# CH32F203VCT6-R1.net
KiCad netlist of a schematic drawn in Altium Designer
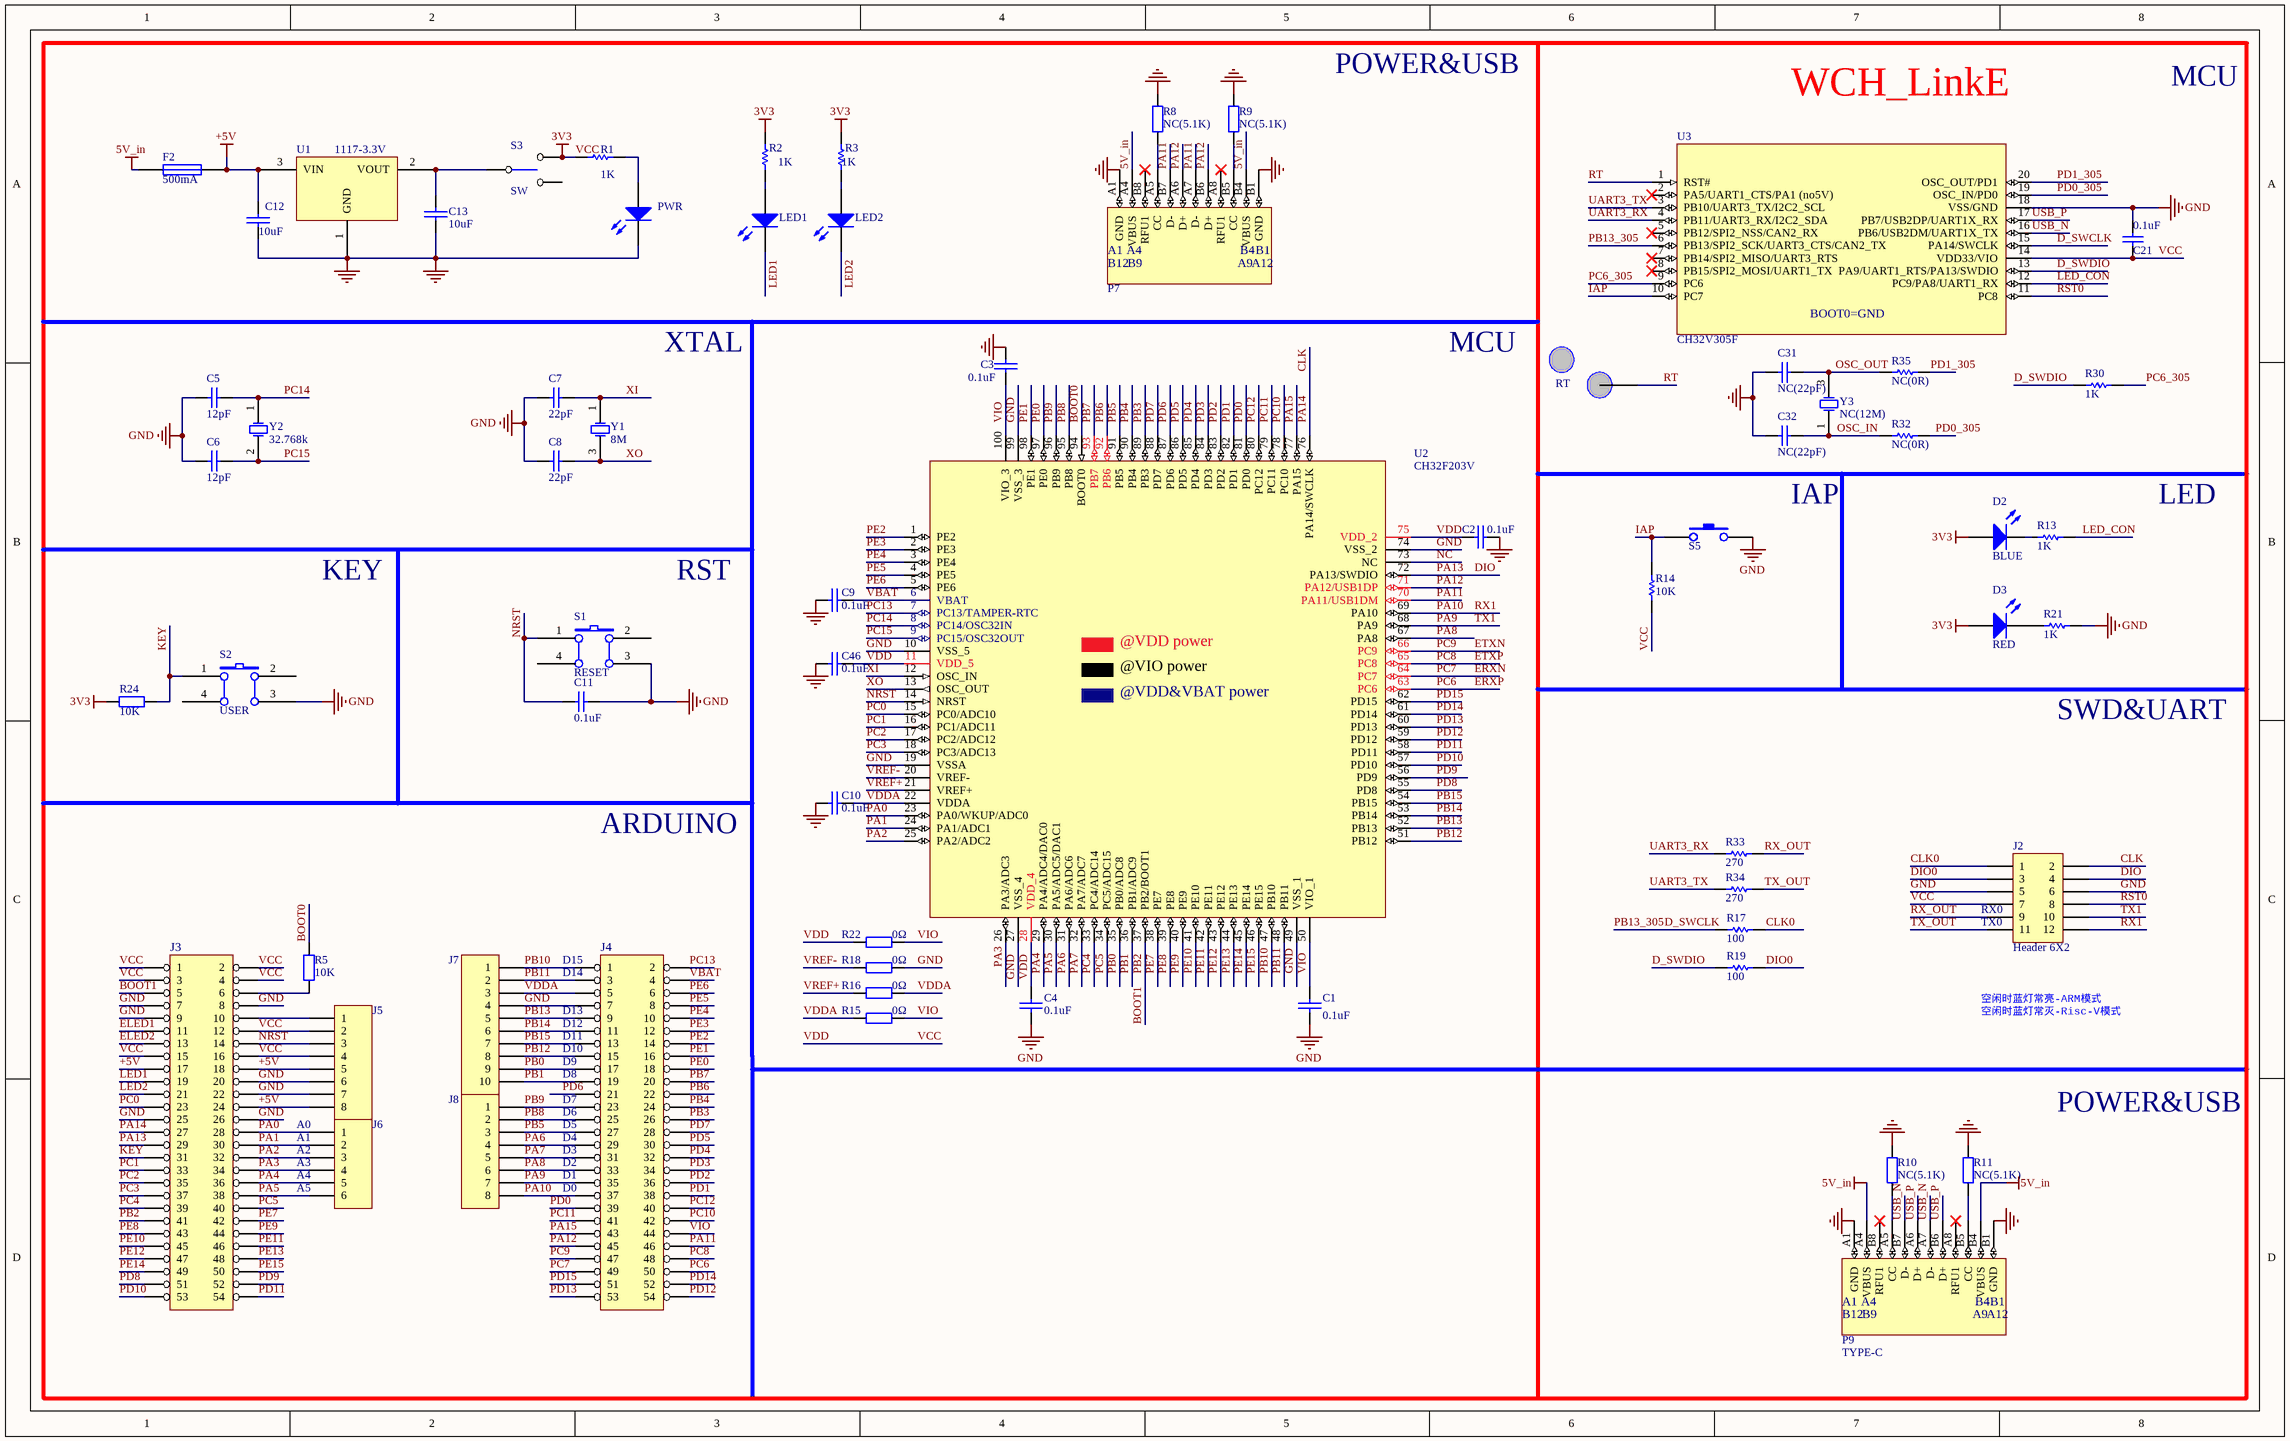
[diagram p0: CH32F203VCT6-R1.SchDoc]

(export (version "E")
  (design (tool "Eeschema 10.0.6"))
  (components
    (comp (ref "C1")
      (value "0.1uF")
      (footprint "0603_C")
      (description "Capacitor")
      (libsource (lib "*") (part "CAP"))
    )
    (comp (ref "C2")
      (value "0.1uF")
      (footprint "0603_C")
      (description "Capacitor")
      (libsource (lib "*") (part "CAP"))
    )
    (comp (ref "C3")
      (value "0.1uF")
      (footprint "0603_C")
      (description "Capacitor")
      (libsource (lib "*") (part "CAP"))
    )
    (comp (ref "C4")
      (value "0.1uF")
      (footprint "0603_C")
      (description "Capacitor")
      (libsource (lib "*") (part "CAP"))
    )
    (comp (ref "C5")
      (value "12pF")
      (footprint "0603_C")
      (description "Capacitor")
      (libsource (lib "Miscellaneous Devices") (part "Cap"))
    )
    (comp (ref "C6")
      (value "12pF")
      (footprint "0603_C")
      (description "Capacitor")
      (libsource (lib "Miscellaneous Devices") (part "Cap"))
    )
    (comp (ref "C7")
      (value "22pF")
      (footprint "0603_C")
      (description "Capacitor")
      (libsource (lib "Miscellaneous Devices") (part "Cap"))
    )
    (comp (ref "C8")
      (value "22pF")
      (footprint "0603_C")
      (description "Capacitor")
      (libsource (lib "Miscellaneous Devices") (part "Cap"))
    )
    (comp (ref "C9")
      (value "0.1uF")
      (footprint "0603_C")
      (description "Capacitor")
      (libsource (lib "*") (part "CAP"))
    )
    (comp (ref "C10")
      (value "0.1uF")
      (footprint "0603_C")
      (description "Capacitor")
      (libsource (lib "*") (part "CAP"))
    )
    (comp (ref "C11")
      (value "0.1uF")
      (footprint "0603_C")
      (description "Capacitor")
      (libsource (lib "Miscellaneous Devices") (part "Cap"))
    )
    (comp (ref "C12")
      (value "10uF")
      (footprint "3216_C")
      (description "Capacitor")
      (libsource (lib "*") (part "CAP"))
    )
    (comp (ref "C13")
      (value "10uF")
      (footprint "3216_C")
      (description "Capacitor")
      (libsource (lib "*") (part "CAP"))
    )
    (comp (ref "C21")
      (value "0.1uF")
      (footprint "0603_C")
      (description "Capacitor")
      (libsource (lib "Miscellaneous Devices") (part "Cap"))
    )
    (comp (ref "C31")
      (value "NC(22pF)")
      (footprint "0603_C")
      (description "Capacitor")
      (fields (field (name "PUBLISHER") "Altium Limited"))
      (libsource (lib "*") (part "Cap"))
    )
    (comp (ref "C32")
      (value "NC(22pF)")
      (footprint "0603_C")
      (description "Capacitor")
      (fields (field (name "PUBLISHER") "Altium Limited"))
      (libsource (lib "*") (part "Cap"))
    )
    (comp (ref "C46")
      (value "0.1uF")
      (footprint "0603_C")
      (description "Capacitor")
      (libsource (lib "*") (part "CAP"))
    )
    (comp (ref "D2")
      (value "BLUE")
      (footprint "0603+")
      (description "Typical RED, GREEN, YELLOW, AMBER GaAs LED")
      (fields (field (name "PUBLISHER") "Altium Limited"))
      (libsource (lib "MYLIB") (part "D0603"))
    )
    (comp (ref "D3")
      (value "RED")
      (footprint "0603+")
      (description "Typical RED, GREEN, YELLOW, AMBER GaAs LED")
      (fields (field (name "PUBLISHER") "Altium Limited"))
      (libsource (lib "MYLIB") (part "D0603"))
    )
    (comp (ref "F2")
      (value "500mA")
      (footprint "0805")
      (description "Fuse")
      (libsource (lib "*") (part "FUSE1"))
    )
    (comp (ref "J2")
      (value "Header 6X2")
      (footprint "IDC12-2.54mm")
      (description "Header, 6-Pin, Dual row")
      (fields (field (name "PUBLISHER") "Altium Limited"))
      (libsource (lib "Miscellaneous Connectors") (part "Header 6X2"))
    )
    (comp (ref "J3")
      (value "HEADER 27x2")
      (footprint "MYPCB:IDC54-2.54MM")
      (description "Header, 27-Pin, Dual row")
      (libsource (lib "wch_sch_others") (part "HEADER 27x2"))
    )
    (comp (ref "J4")
      (value "HEADER 27x2")
      (footprint "MYPCB:IDC54-2.54MM")
      (description "Header, 27-Pin, Dual row")
      (libsource (lib "wch_sch_others") (part "HEADER 27x2"))
    )
    (comp (ref "J5")
      (value "Header 8")
      (footprint "SIP8-2.54mm")
      (description "Header, 8-Pin")
      (fields (field (name "PUBLISHER") "Altium Limited"))
      (libsource (lib "") (part "Header 8_1"))
    )
    (comp (ref "J6")
      (value "Header 6")
      (footprint "SIP6-2.54MM")
      (description "Header, 6-Pin")
      (fields (field (name "PUBLISHER") "Altium Limited"))
      (libsource (lib "Miscellaneous Connectors") (part "Header 6"))
    )
    (comp (ref "J7")
      (value "Header 10")
      (footprint "SIP10-2.54mm")
      (description "Header, 10-Pin")
      (fields (field (name "PUBLISHER") "Altium Limited"))
      (libsource (lib "Miscellaneous Connectors") (part "Header 10"))
    )
    (comp (ref "J8")
      (value "Header 8")
      (footprint "SIP8-2.54mm")
      (description "Header, 8-Pin")
      (fields (field (name "PUBLISHER") "Altium Limited"))
      (libsource (lib "Miscellaneous Connectors") (part "Header 8"))
    )
    (comp (ref "LED1")
      (value "LED1   blue")
      (footprint "0603+")
      (description "Typical INFRARED GaAs LED")
      (fields (field (name "PUBLISHER") "Altium Limited"))
      (libsource (lib "Miscellaneous Devices") (part "LED0"))
    )
    (comp (ref "LED2")
      (value "LED2  blue")
      (footprint "0603+")
      (description "Typical INFRARED GaAs LED")
      (fields (field (name "PUBLISHER") "Altium Limited"))
      (libsource (lib "Miscellaneous Devices") (part "LED0"))
    )
    (comp (ref "P7")
      (value "USBFS")
      (footprint "TYPE-C-Receptacle-2.0")
      (libsource (lib "*") (part "TYPE-C1"))
    )
    (comp (ref "P9")
      (value "TYPE-C")
      (footprint "TYPE-C-Receptacle-2.0")
      (libsource (lib "*") (part "TYPE-C1"))
    )
    (comp (ref "PWR")
      (value "POWER  red")
      (footprint "0603+")
      (description "Typical INFRARED GaAs LED")
      (fields (field (name "PUBLISHER") "Altium Limited"))
      (libsource (lib "Miscellaneous Devices") (part "LED0"))
    )
    (comp (ref "R1")
      (value "1K")
      (footprint "0603")
      (description "Semiconductor Resistor")
      (libsource (lib "Miscellaneous Devices") (part "Res Semi"))
    )
    (comp (ref "R2")
      (value "1K")
      (footprint "0603")
      (description "Semiconductor Resistor")
      (libsource (lib "Miscellaneous Devices") (part "Res Semi"))
    )
    (comp (ref "R3")
      (value "1K")
      (footprint "0603")
      (description "Semiconductor Resistor")
      (libsource (lib "Miscellaneous Devices") (part "Res Semi"))
    )
    (comp (ref "R5")
      (value "10K")
      (footprint "0603")
      (description "Resistor")
      (libsource (lib "Miscellaneous Devices") (part "Res2"))
    )
    (comp (ref "R8")
      (value "NC(5.1K)")
      (footprint "0603")
      (description "Resistor")
      (libsource (lib "") (part "Res2_2"))
    )
    (comp (ref "R9")
      (value "NC(5.1K)")
      (footprint "0603")
      (description "Resistor")
      (libsource (lib "") (part "Res2_2"))
    )
    (comp (ref "R10")
      (value "NC(5.1K)")
      (footprint "0603")
      (description "Resistor")
      (libsource (lib "Miscellaneous Devices") (part "Res2"))
    )
    (comp (ref "R11")
      (value "NC(5.1K)")
      (footprint "0603")
      (description "Resistor")
      (libsource (lib "Miscellaneous Devices") (part "Res2"))
    )
    (comp (ref "R13")
      (value "1K")
      (footprint "0603")
      (description "Resistor")
      (fields (field (name "PUBLISHER") "Altium Limited"))
      (libsource (lib "MYLIB") (part "0603-1"))
    )
    (comp (ref "R14")
      (value "10K")
      (footprint "0603")
      (description "Resistor")
      (fields (field (name "PUBLISHER") "Altium Limited"))
      (libsource (lib "MYLIB") (part "0603-1"))
    )
    (comp (ref "R15")
      (value "0Ω")
      (footprint "0603")
      (description "Resistor")
      (libsource (lib "") (part "Res2_1"))
    )
    (comp (ref "R16")
      (value "0Ω")
      (footprint "0603")
      (description "Resistor")
      (libsource (lib "") (part "Res2_1"))
    )
    (comp (ref "R17")
      (value "100")
      (footprint "0603")
      (description "Resistor")
      (fields (field (name "PUBLISHER") "Altium Limited"))
      (libsource (lib "MYLIB") (part "0603-1"))
    )
    (comp (ref "R18")
      (value "0Ω")
      (footprint "0603")
      (description "Resistor")
      (libsource (lib "") (part "Res2_1"))
    )
    (comp (ref "R19")
      (value "100")
      (footprint "0603")
      (description "Resistor")
      (fields (field (name "PUBLISHER") "Altium Limited"))
      (libsource (lib "MYLIB") (part "0603-1"))
    )
    (comp (ref "R21")
      (value "1K")
      (footprint "0603")
      (description "Resistor")
      (fields (field (name "PUBLISHER") "Altium Limited"))
      (libsource (lib "MYLIB") (part "0603-1"))
    )
    (comp (ref "R22")
      (value "0Ω")
      (footprint "0603")
      (description "Resistor")
      (libsource (lib "") (part "Res2_1"))
    )
    (comp (ref "R24")
      (value "10K")
      (footprint "0603")
      (description "Resistor")
      (libsource (lib "") (part "Res2_1"))
    )
    (comp (ref "R30")
      (value "1K")
      (footprint "0603")
      (description "Resistor")
      (fields (field (name "PUBLISHER") "Altium Limited"))
      (libsource (lib "MYLIB") (part "0603-1"))
    )
    (comp (ref "R32")
      (value "NC(0R)")
      (footprint "0603")
      (description "Resistor")
      (fields (field (name "PUBLISHER") "Altium Limited"))
      (libsource (lib "MYLIB") (part "0603-1"))
    )
    (comp (ref "R33")
      (value "270")
      (footprint "0603")
      (description "Resistor")
      (fields (field (name "PUBLISHER") "Altium Limited"))
      (libsource (lib "MYLIB") (part "0603-1"))
    )
    (comp (ref "R34")
      (value "270")
      (footprint "0603")
      (description "Resistor")
      (fields (field (name "PUBLISHER") "Altium Limited"))
      (libsource (lib "MYLIB") (part "0603-1"))
    )
    (comp (ref "R35")
      (value "NC(0R)")
      (footprint "0603")
      (description "Resistor")
      (fields (field (name "PUBLISHER") "Altium Limited"))
      (libsource (lib "MYLIB") (part "0603-1"))
    )
    (comp (ref "RT")
      (value "Testpoint")
      (footprint "TESTPOINT1")
      (description "测试点")
      (libsource (lib "wch_sch_others") (part "Testpoint"))
    )
    (comp (ref "S1")
      (value "RESET")
      (footprint "KEYX")
      (description "SE PUSHBUTTON")
      (libsource (lib "Documents") (part "SW PUSHBUTTON"))
    )
    (comp (ref "S2")
      (value "USER")
      (footprint "KEYX")
      (description "SE PUSHBUTTON")
      (libsource (lib "Documents") (part "SW PUSHBUTTON"))
    )
    (comp (ref "S3") (value "SW") (footprint "SW1") (libsource (lib "MYSCH") (part "SW")))
    (comp (ref "S5") (value "KEY") (footprint "贴片按键") (libsource (lib "*") (part "KEY")))
    (comp (ref "U1")
      (value "1117-3.3V")
      (footprint "SOT-223")
      (libsource (lib "wch_sch_others") (part "1117-3.3V"))
    )
    (comp (ref "U2")
      (value "CH32F203V")
      (footprint "LQFP100")
      (description "ARM M3 HD-MCU, 144MHz, 8*UART, 10*Timer, 4*OPA")
      (libsource (lib "CHXXX") (part "CH32F203V"))
    )
    (comp (ref "U3")
      (value "CH32V305F")
      (footprint "TSSOP20")
      (description "RISC-V FPU HD-MCU, 144MHz, USB_480M, CAN, UART*2, SPI")
      (libsource (lib "CHXXX") (part "CH32V305F"))
    )
    (comp (ref "Y1")
      (value "8M")
      (footprint "XT3225")
      (description "Crystal Oscillator")
      (fields (field (name "PUBLISHER") "Altium Limited"))
      (libsource (lib "") (part "XTAL_1"))
    )
    (comp (ref "Y2")
      (value "32.768k")
      (footprint "FC-135")
      (description "Crystal Oscillator")
      (fields (field (name "PUBLISHER") "Altium Limited"))
      (libsource (lib "Miscellaneous Devices") (part "XTAL"))
    )
    (comp (ref "Y3")
      (value "NC(12M)")
      (footprint "XT3225")
      (description "Crystal Oscillator")
      (libsource (lib "*") (part "XTAL"))
    )
  )
  (nets
    (net (code "1") (name "+5V") (class "Default")
      (node (ref "C12") (pin "1") (pinfunction "1_1") (pintype "passive"))
      (node (ref "F2") (pin "2") (pinfunction "2_2") (pintype "passive"))
      (node (ref "J3") (pin "17") (pinfunction "17_17") (pintype "passive"))
      (node (ref "J3") (pin "18") (pinfunction "18_18") (pintype "passive"))
      (node (ref "J3") (pin "24") (pinfunction "24_24") (pintype "passive"))
      (node (ref "J5") (pin "5") (pinfunction "5_5") (pintype "passive"))
      (node (ref "J5") (pin "8") (pinfunction "8_8") (pintype "passive"))
      (node (ref "U1") (pin "3") (pinfunction "VIN_3") (pintype "passive"))
    )
    (net (code "2") (name "/BOOT0") (class "Default")
      (node (ref "R5") (pin "2") (pinfunction "2_2") (pintype "passive"))
      (node (ref "U2") (pin "94") (pinfunction "BOOT0_94") (pintype "input"))
    )
    (net (code "3") (name "/BOOT1") (class "Default")
      (node (ref "J3") (pin "41") (pinfunction "41_41") (pintype "passive"))
      (node (ref "J3") (pin "5") (pinfunction "5_5") (pintype "passive"))
      (node (ref "U2") (pin "37") (pinfunction "PB2/BOOT1_37") (pintype "bidirectional"))
    )
    (net (code "4") (name "/CLK") (class "Default")
      (node (ref "J2") (pin "2") (pinfunction "2_2") (pintype "passive"))
      (node (ref "J3") (pin "27") (pinfunction "27_27") (pintype "passive"))
      (node (ref "U2") (pin "76") (pinfunction "PA14/SWCLK_76") (pintype "bidirectional"))
    )
    (net (code "5") (name "/CLK0") (class "Default")
      (node (ref "J2") (pin "1") (pinfunction "1_1") (pintype "passive"))
      (node (ref "R17") (pin "1") (pinfunction "1_1") (pintype "passive"))
    )
    (net (code "6") (name "/DIO") (class "Default")
      (node (ref "J2") (pin "4") (pinfunction "4_4") (pintype "passive"))
      (node (ref "J3") (pin "29") (pinfunction "29_29") (pintype "passive"))
      (node (ref "U2") (pin "72") (pinfunction "PA13/SWDIO_72") (pintype "bidirectional"))
    )
    (net (code "7") (name "/DIO0") (class "Default")
      (node (ref "J2") (pin "3") (pinfunction "3_3") (pintype "passive"))
      (node (ref "R19") (pin "1") (pinfunction "1_1") (pintype "passive"))
    )
    (net (code "8") (name "/D_SWCLK") (class "Default")
      (node (ref "R17") (pin "2") (pinfunction "2_2") (pintype "passive"))
      (node (ref "U3") (pin "15") (pinfunction "PA14/SWCLK_15") (pintype "bidirectional"))
      (node (ref "U3") (pin "6") (pinfunction "PB13/SPI2_SCK/UART3_CTS/CAN2_TX_6") (pintype "bidirectional"))
    )
    (net (code "9") (name "/D_SWDIO") (class "Default")
      (node (ref "R19") (pin "2") (pinfunction "2_2") (pintype "passive"))
      (node (ref "R30") (pin "1") (pinfunction "1_1") (pintype "passive"))
      (node (ref "U3") (pin "13") (pinfunction "PA9/UART1_RTS/PA13/SWDIO_13") (pintype "bidirectional"))
    )
    (net (code "10") (name "/ELED1") (class "Default")
      (node (ref "J3") (pin "11") (pinfunction "11_11") (pintype "passive"))
    )
    (net (code "11") (name "/ELED2") (class "Default")
      (node (ref "J3") (pin "13") (pinfunction "13_13") (pintype "passive"))
    )
    (net (code "12") (name "/ERXN") (class "Default")
      (node (ref "J4") (pin "49") (pinfunction "49_49") (pintype "passive"))
      (node (ref "U2") (pin "64") (pinfunction "PC7_64") (pintype "bidirectional"))
    )
    (net (code "13") (name "/ERXP") (class "Default")
      (node (ref "J4") (pin "50") (pinfunction "50_50") (pintype "passive"))
      (node (ref "U2") (pin "63") (pinfunction "PC6_63") (pintype "bidirectional"))
    )
    (net (code "14") (name "/ETXN") (class "Default")
      (node (ref "J4") (pin "47") (pinfunction "47_47") (pintype "passive"))
      (node (ref "U2") (pin "66") (pinfunction "PC9_66") (pintype "bidirectional"))
    )
    (net (code "15") (name "/ETXP") (class "Default")
      (node (ref "J4") (pin "48") (pinfunction "48_48") (pintype "passive"))
      (node (ref "U2") (pin "65") (pinfunction "PC8_65") (pintype "bidirectional"))
    )
    (net (code "16") (name "/IAP") (class "Default")
      (node (ref "R14") (pin "1") (pinfunction "1_1") (pintype "passive"))
      (node (ref "S5") (pin "1") (pinfunction "1_1") (pintype "passive"))
      (node (ref "U3") (pin "10") (pinfunction "PC7_10") (pintype "bidirectional"))
    )
    (net (code "17") (name "/KEY") (class "Default")
      (node (ref "J3") (pin "31") (pinfunction "31_31") (pintype "passive"))
      (node (ref "R24") (pin "1") (pinfunction "1_1") (pintype "passive"))
      (node (ref "S2") (pin "1") (pinfunction "A0_1") (pintype "passive"))
    )
    (net (code "18") (name "/LED1") (class "Default")
      (node (ref "J3") (pin "19") (pinfunction "19_19") (pintype "passive"))
      (node (ref "LED1") (pin "2") (pinfunction "K_2") (pintype "passive"))
    )
    (net (code "19") (name "/LED2") (class "Default")
      (node (ref "J3") (pin "21") (pinfunction "21_21") (pintype "passive"))
      (node (ref "LED2") (pin "2") (pinfunction "K_2") (pintype "passive"))
    )
    (net (code "20") (name "/LED_CON") (class "Default")
      (node (ref "R13") (pin "1") (pinfunction "1_1") (pintype "passive"))
      (node (ref "U3") (pin "12") (pinfunction "PC9/PA8/UART1_RX_12") (pintype "bidirectional"))
    )
    (net (code "21") (name "/NC") (class "Default")
      (node (ref "U2") (pin "73") (pinfunction "NC_73") (pintype "tri_state"))
    )
    (net (code "22") (name "/NRST") (class "Default")
      (node (ref "C11") (pin "2") (pinfunction "2_2") (pintype "passive"))
      (node (ref "J3") (pin "14") (pinfunction "14_14") (pintype "passive"))
      (node (ref "J5") (pin "3") (pinfunction "3_3") (pintype "passive"))
      (node (ref "S1") (pin "1") (pinfunction "A0_1") (pintype "passive"))
      (node (ref "U2") (pin "14") (pinfunction "NRST_14") (pintype "input"))
    )
    (net (code "23") (name "/OSC_IN") (class "Default")
      (node (ref "C32") (pin "2") (pinfunction "2_2") (pintype "passive"))
      (node (ref "R32") (pin "2") (pinfunction "2_2") (pintype "passive"))
      (node (ref "Y3") (pin "1") (pinfunction "OSC1_1") (pintype "passive"))
    )
    (net (code "24") (name "/OSC_OUT") (class "Default")
      (node (ref "C31") (pin "2") (pinfunction "2_2") (pintype "passive"))
      (node (ref "R35") (pin "2") (pinfunction "2_2") (pintype "passive"))
      (node (ref "Y3") (pin "3") (pinfunction "OSC2_3") (pintype "passive"))
    )
    (net (code "25") (name "/PA0") (class "Default")
      (node (ref "J3") (pin "28") (pinfunction "28_28") (pintype "passive"))
      (node (ref "J6") (pin "1") (pinfunction "1_1") (pintype "passive"))
      (node (ref "U2") (pin "23") (pinfunction "PA0/WKUP/ADC0_23") (pintype "bidirectional"))
    )
    (net (code "26") (name "/PA1") (class "Default")
      (node (ref "J3") (pin "30") (pinfunction "30_30") (pintype "passive"))
      (node (ref "J6") (pin "2") (pinfunction "2_2") (pintype "passive"))
      (node (ref "U2") (pin "24") (pinfunction "PA1/ADC1_24") (pintype "bidirectional"))
    )
    (net (code "27") (name "/PA2") (class "Default")
      (node (ref "J3") (pin "32") (pinfunction "32_32") (pintype "passive"))
      (node (ref "J6") (pin "3") (pinfunction "3_3") (pintype "passive"))
      (node (ref "U2") (pin "25") (pinfunction "PA2/ADC2_25") (pintype "bidirectional"))
    )
    (net (code "28") (name "/PA3") (class "Default")
      (node (ref "J3") (pin "34") (pinfunction "34_34") (pintype "passive"))
      (node (ref "J6") (pin "4") (pinfunction "4_4") (pintype "passive"))
      (node (ref "U2") (pin "26") (pinfunction "PA3/ADC3_26") (pintype "bidirectional"))
    )
    (net (code "29") (name "/PA4") (class "Default")
      (node (ref "J3") (pin "36") (pinfunction "36_36") (pintype "passive"))
      (node (ref "J6") (pin "5") (pinfunction "5_5") (pintype "passive"))
      (node (ref "U2") (pin "29") (pinfunction "PA4/ADC4/DAC0_29") (pintype "bidirectional"))
    )
    (net (code "30") (name "/PA5") (class "Default")
      (node (ref "J3") (pin "38") (pinfunction "38_38") (pintype "passive"))
      (node (ref "J6") (pin "6") (pinfunction "6_6") (pintype "passive"))
      (node (ref "U2") (pin "30") (pinfunction "PA5/ADC5/DAC1_30") (pintype "bidirectional"))
    )
    (net (code "31") (name "/PA6") (class "Default")
      (node (ref "J4") (pin "29") (pinfunction "29_29") (pintype "passive"))
      (node (ref "J8") (pin "4") (pinfunction "4_4") (pintype "passive"))
      (node (ref "U2") (pin "31") (pinfunction "PA6/ADC6_31") (pintype "bidirectional"))
    )
    (net (code "32") (name "/PA7") (class "Default")
      (node (ref "J4") (pin "31") (pinfunction "31_31") (pintype "passive"))
      (node (ref "J8") (pin "5") (pinfunction "5_5") (pintype "passive"))
      (node (ref "U2") (pin "32") (pinfunction "PA7/ADC7_32") (pintype "bidirectional"))
    )
    (net (code "33") (name "/PA8") (class "Default")
      (node (ref "J4") (pin "33") (pinfunction "33_33") (pintype "passive"))
      (node (ref "J8") (pin "6") (pinfunction "6_6") (pintype "passive"))
      (node (ref "U2") (pin "67") (pinfunction "PA8_67") (pintype "bidirectional"))
    )
    (net (code "34") (name "/PA9") (class "Default")
      (node (ref "J2") (pin "10") (pinfunction "10_10") (pintype "passive"))
      (node (ref "J4") (pin "35") (pinfunction "35_35") (pintype "passive"))
      (node (ref "J8") (pin "7") (pinfunction "7_7") (pintype "passive"))
      (node (ref "U2") (pin "68") (pinfunction "PA9_68") (pintype "bidirectional"))
    )
    (net (code "35") (name "/PA10") (class "Default")
      (node (ref "J2") (pin "12") (pinfunction "12_12") (pintype "passive"))
      (node (ref "J4") (pin "37") (pinfunction "37_37") (pintype "passive"))
      (node (ref "J8") (pin "8") (pinfunction "8_8") (pintype "passive"))
      (node (ref "U2") (pin "69") (pinfunction "PA10_69") (pintype "bidirectional"))
    )
    (net (code "36") (name "/PA11") (class "Default")
      (node (ref "J4") (pin "46") (pinfunction "46_46") (pintype "passive"))
      (node (ref "P7") (pin "A7") (pinfunction "D-_A7") (pintype "bidirectional"))
      (node (ref "P7") (pin "B7") (pinfunction "D-_B7") (pintype "bidirectional"))
      (node (ref "U2") (pin "70") (pinfunction "PA11/USB1DM_70") (pintype "bidirectional"))
    )
    (net (code "37") (name "/PA12") (class "Default")
      (node (ref "J4") (pin "45") (pinfunction "45_45") (pintype "passive"))
      (node (ref "P7") (pin "A6") (pinfunction "D+_A6") (pintype "bidirectional"))
      (node (ref "P7") (pin "B6") (pinfunction "D+_B6") (pintype "bidirectional"))
      (node (ref "U2") (pin "71") (pinfunction "PA12/USB1DP_71") (pintype "bidirectional"))
    )
    (net (code "38") (name "/PA15") (class "Default")
      (node (ref "J4") (pin "43") (pinfunction "43_43") (pintype "passive"))
      (node (ref "U2") (pin "77") (pinfunction "PA15_77") (pintype "bidirectional"))
    )
    (net (code "39") (name "/PB0") (class "Default")
      (node (ref "J4") (pin "17") (pinfunction "17_17") (pintype "passive"))
      (node (ref "J7") (pin "9") (pinfunction "9_9") (pintype "passive"))
      (node (ref "U2") (pin "35") (pinfunction "PB0/ADC8_35") (pintype "bidirectional"))
    )
    (net (code "40") (name "/PB1") (class "Default")
      (node (ref "J4") (pin "19") (pinfunction "19_19") (pintype "passive"))
      (node (ref "J7") (pin "10") (pinfunction "10_10") (pintype "passive"))
      (node (ref "U2") (pin "36") (pinfunction "PB1/ADC9_36") (pintype "bidirectional"))
    )
    (net (code "41") (name "/PB3") (class "Default")
      (node (ref "J4") (pin "26") (pinfunction "26_26") (pintype "passive"))
      (node (ref "U2") (pin "89") (pinfunction "PB3_89") (pintype "bidirectional"))
    )
    (net (code "42") (name "/PB4") (class "Default")
      (node (ref "J4") (pin "24") (pinfunction "24_24") (pintype "passive"))
      (node (ref "U2") (pin "90") (pinfunction "PB4_90") (pintype "bidirectional"))
    )
    (net (code "43") (name "/PB5") (class "Default")
      (node (ref "J4") (pin "27") (pinfunction "27_27") (pintype "passive"))
      (node (ref "J8") (pin "3") (pinfunction "3_3") (pintype "passive"))
      (node (ref "U2") (pin "91") (pinfunction "PB5_91") (pintype "bidirectional"))
    )
    (net (code "44") (name "/PB6") (class "Default")
      (node (ref "J4") (pin "22") (pinfunction "22_22") (pintype "passive"))
      (node (ref "U2") (pin "92") (pinfunction "PB6_92") (pintype "bidirectional"))
    )
    (net (code "45") (name "/PB7") (class "Default")
      (node (ref "J4") (pin "20") (pinfunction "20_20") (pintype "passive"))
      (node (ref "U2") (pin "93") (pinfunction "PB7_93") (pintype "bidirectional"))
    )
    (net (code "46") (name "/PB8") (class "Default")
      (node (ref "J4") (pin "25") (pinfunction "25_25") (pintype "passive"))
      (node (ref "J8") (pin "2") (pinfunction "2_2") (pintype "passive"))
      (node (ref "U2") (pin "95") (pinfunction "PB8_95") (pintype "bidirectional"))
    )
    (net (code "47") (name "/PB9") (class "Default")
      (node (ref "J4") (pin "23") (pinfunction "23_23") (pintype "passive"))
      (node (ref "J8") (pin "1") (pinfunction "1_1") (pintype "passive"))
      (node (ref "U2") (pin "96") (pinfunction "PB9_96") (pintype "bidirectional"))
    )
    (net (code "48") (name "/PB10") (class "Default")
      (node (ref "J4") (pin "1") (pinfunction "1_1") (pintype "passive"))
      (node (ref "J7") (pin "1") (pinfunction "1_1") (pintype "passive"))
      (node (ref "U2") (pin "47") (pinfunction "PB10_47") (pintype "bidirectional"))
    )
    (net (code "49") (name "/PB11") (class "Default")
      (node (ref "J4") (pin "3") (pinfunction "3_3") (pintype "passive"))
      (node (ref "J7") (pin "2") (pinfunction "2_2") (pintype "passive"))
      (node (ref "U2") (pin "48") (pinfunction "PB11_48") (pintype "bidirectional"))
    )
    (net (code "50") (name "/PB12") (class "Default")
      (node (ref "J4") (pin "15") (pinfunction "15_15") (pintype "passive"))
      (node (ref "J7") (pin "8") (pinfunction "8_8") (pintype "passive"))
      (node (ref "U2") (pin "51") (pinfunction "PB12_51") (pintype "bidirectional"))
    )
    (net (code "51") (name "/PB13") (class "Default")
      (node (ref "J4") (pin "9") (pinfunction "9_9") (pintype "passive"))
      (node (ref "J7") (pin "5") (pinfunction "5_5") (pintype "passive"))
      (node (ref "U2") (pin "52") (pinfunction "PB13_52") (pintype "bidirectional"))
    )
    (net (code "52") (name "/PB14") (class "Default")
      (node (ref "J4") (pin "11") (pinfunction "11_11") (pintype "passive"))
      (node (ref "J7") (pin "6") (pinfunction "6_6") (pintype "passive"))
      (node (ref "U2") (pin "53") (pinfunction "PB14_53") (pintype "bidirectional"))
    )
    (net (code "53") (name "/PB15") (class "Default")
      (node (ref "J4") (pin "13") (pinfunction "13_13") (pintype "passive"))
      (node (ref "J7") (pin "7") (pinfunction "7_7") (pintype "passive"))
      (node (ref "U2") (pin "54") (pinfunction "PB15_54") (pintype "bidirectional"))
    )
    (net (code "54") (name "/PC0") (class "Default")
      (node (ref "J3") (pin "23") (pinfunction "23_23") (pintype "passive"))
      (node (ref "U2") (pin "15") (pinfunction "PC0/ADC10_15") (pintype "bidirectional"))
    )
    (net (code "55") (name "/PC1") (class "Default")
      (node (ref "J3") (pin "33") (pinfunction "33_33") (pintype "passive"))
      (node (ref "U2") (pin "16") (pinfunction "PC1/ADC11_16") (pintype "bidirectional"))
    )
    (net (code "56") (name "/PC2") (class "Default")
      (node (ref "J3") (pin "35") (pinfunction "35_35") (pintype "passive"))
      (node (ref "U2") (pin "17") (pinfunction "PC2/ADC12_17") (pintype "bidirectional"))
    )
    (net (code "57") (name "/PC3") (class "Default")
      (node (ref "J3") (pin "37") (pinfunction "37_37") (pintype "passive"))
      (node (ref "U2") (pin "18") (pinfunction "PC3/ADC13_18") (pintype "bidirectional"))
    )
    (net (code "58") (name "/PC4") (class "Default")
      (node (ref "J3") (pin "39") (pinfunction "39_39") (pintype "passive"))
      (node (ref "U2") (pin "33") (pinfunction "PC4/ADC14_33") (pintype "bidirectional"))
    )
    (net (code "59") (name "/PC5") (class "Default")
      (node (ref "J3") (pin "40") (pinfunction "40_40") (pintype "passive"))
      (node (ref "U2") (pin "34") (pinfunction "PC5/ADC15_34") (pintype "bidirectional"))
    )
    (net (code "60") (name "/PC6_305") (class "Default")
      (node (ref "R30") (pin "2") (pinfunction "2_2") (pintype "passive"))
      (node (ref "U3") (pin "9") (pinfunction "PC6_9") (pintype "bidirectional"))
    )
    (net (code "61") (name "/PC10") (class "Default")
      (node (ref "J4") (pin "42") (pinfunction "42_42") (pintype "passive"))
      (node (ref "U2") (pin "78") (pinfunction "PC10_78") (pintype "bidirectional"))
    )
    (net (code "62") (name "/PC11") (class "Default")
      (node (ref "J4") (pin "41") (pinfunction "41_41") (pintype "passive"))
      (node (ref "U2") (pin "79") (pinfunction "PC11_79") (pintype "bidirectional"))
    )
    (net (code "63") (name "/PC12") (class "Default")
      (node (ref "J4") (pin "40") (pinfunction "40_40") (pintype "passive"))
      (node (ref "U2") (pin "80") (pinfunction "PC12_80") (pintype "bidirectional"))
    )
    (net (code "64") (name "/PC13") (class "Default")
      (node (ref "J4") (pin "2") (pinfunction "2_2") (pintype "passive"))
      (node (ref "U2") (pin "7") (pinfunction "PC13/TAMPER-RTC_7") (pintype "bidirectional"))
    )
    (net (code "65") (name "/PC14") (class "Default")
      (node (ref "C5") (pin "1") (pinfunction "1_1") (pintype "passive"))
      (node (ref "U2") (pin "8") (pinfunction "PC14/OSC32IN_8") (pintype "bidirectional"))
      (node (ref "Y2") (pin "1") (pinfunction "OSC1_1") (pintype "passive"))
    )
    (net (code "66") (name "/PC15") (class "Default")
      (node (ref "C6") (pin "1") (pinfunction "1_1") (pintype "passive"))
      (node (ref "U2") (pin "9") (pinfunction "PC15/OSC32OUT_9") (pintype "bidirectional"))
      (node (ref "Y2") (pin "2") (pinfunction "OSC2_2") (pintype "passive"))
    )
    (net (code "67") (name "/PD0") (class "Default")
      (node (ref "J4") (pin "39") (pinfunction "39_39") (pintype "passive"))
      (node (ref "U2") (pin "81") (pinfunction "PD0_81") (pintype "bidirectional"))
    )
    (net (code "68") (name "/PD0_305") (class "Default")
      (node (ref "R32") (pin "1") (pinfunction "1_1") (pintype "passive"))
      (node (ref "U3") (pin "19") (pinfunction "OSC_IN/PD0_19") (pintype "bidirectional"))
    )
    (net (code "69") (name "/PD1") (class "Default")
      (node (ref "J4") (pin "38") (pinfunction "38_38") (pintype "passive"))
      (node (ref "U2") (pin "82") (pinfunction "PD1_82") (pintype "bidirectional"))
    )
    (net (code "70") (name "/PD1_305") (class "Default")
      (node (ref "R35") (pin "1") (pinfunction "1_1") (pintype "passive"))
      (node (ref "U3") (pin "20") (pinfunction "OSC_OUT/PD1_20") (pintype "bidirectional"))
    )
    (net (code "71") (name "/PD2") (class "Default")
      (node (ref "J4") (pin "36") (pinfunction "36_36") (pintype "passive"))
      (node (ref "U2") (pin "83") (pinfunction "PD2_83") (pintype "bidirectional"))
    )
    (net (code "72") (name "/PD3") (class "Default")
      (node (ref "J4") (pin "34") (pinfunction "34_34") (pintype "passive"))
      (node (ref "U2") (pin "84") (pinfunction "PD3_84") (pintype "bidirectional"))
    )
    (net (code "73") (name "/PD4") (class "Default")
      (node (ref "J4") (pin "32") (pinfunction "32_32") (pintype "passive"))
      (node (ref "U2") (pin "85") (pinfunction "PD4_85") (pintype "bidirectional"))
    )
    (net (code "74") (name "/PD5") (class "Default")
      (node (ref "J4") (pin "30") (pinfunction "30_30") (pintype "passive"))
      (node (ref "U2") (pin "86") (pinfunction "PD5_86") (pintype "bidirectional"))
    )
    (net (code "75") (name "/PD6") (class "Default")
      (node (ref "J4") (pin "21") (pinfunction "21_21") (pintype "passive"))
      (node (ref "U2") (pin "87") (pinfunction "PD6_87") (pintype "bidirectional"))
    )
    (net (code "76") (name "/PD7") (class "Default")
      (node (ref "J4") (pin "28") (pinfunction "28_28") (pintype "passive"))
      (node (ref "U2") (pin "88") (pinfunction "PD7_88") (pintype "bidirectional"))
    )
    (net (code "77") (name "/PD8") (class "Default")
      (node (ref "J3") (pin "51") (pinfunction "51_51") (pintype "passive"))
      (node (ref "U2") (pin "55") (pinfunction "PD8_55") (pintype "bidirectional"))
    )
    (net (code "78") (name "/PD9") (class "Default")
      (node (ref "J3") (pin "52") (pinfunction "52_52") (pintype "passive"))
      (node (ref "U2") (pin "56") (pinfunction "PD9_56") (pintype "bidirectional"))
    )
    (net (code "79") (name "/PD10") (class "Default")
      (node (ref "J3") (pin "53") (pinfunction "53_53") (pintype "passive"))
      (node (ref "U2") (pin "57") (pinfunction "PD10_57") (pintype "bidirectional"))
    )
    (net (code "80") (name "/PD11") (class "Default")
      (node (ref "J3") (pin "54") (pinfunction "54_54") (pintype "passive"))
      (node (ref "U2") (pin "58") (pinfunction "PD11_58") (pintype "bidirectional"))
    )
    (net (code "81") (name "/PD12") (class "Default")
      (node (ref "J4") (pin "54") (pinfunction "54_54") (pintype "passive"))
      (node (ref "U2") (pin "59") (pinfunction "PD12_59") (pintype "bidirectional"))
    )
    (net (code "82") (name "/PD13") (class "Default")
      (node (ref "J4") (pin "53") (pinfunction "53_53") (pintype "passive"))
      (node (ref "U2") (pin "60") (pinfunction "PD13_60") (pintype "bidirectional"))
    )
    (net (code "83") (name "/PD14") (class "Default")
      (node (ref "J4") (pin "52") (pinfunction "52_52") (pintype "passive"))
      (node (ref "U2") (pin "61") (pinfunction "PD14_61") (pintype "bidirectional"))
    )
    (net (code "84") (name "/PD15") (class "Default")
      (node (ref "J4") (pin "51") (pinfunction "51_51") (pintype "passive"))
      (node (ref "U2") (pin "62") (pinfunction "PD15_62") (pintype "bidirectional"))
    )
    (net (code "85") (name "/PE0") (class "Default")
      (node (ref "J4") (pin "18") (pinfunction "18_18") (pintype "passive"))
      (node (ref "U2") (pin "97") (pinfunction "PE0_97") (pintype "bidirectional"))
    )
    (net (code "86") (name "/PE1") (class "Default")
      (node (ref "J4") (pin "16") (pinfunction "16_16") (pintype "passive"))
      (node (ref "U2") (pin "98") (pinfunction "PE1_98") (pintype "bidirectional"))
    )
    (net (code "87") (name "/PE2") (class "Default")
      (node (ref "J4") (pin "14") (pinfunction "14_14") (pintype "passive"))
      (node (ref "U2") (pin "1") (pinfunction "PE2_1") (pintype "bidirectional"))
    )
    (net (code "88") (name "/PE3") (class "Default")
      (node (ref "J4") (pin "12") (pinfunction "12_12") (pintype "passive"))
      (node (ref "U2") (pin "2") (pinfunction "PE3_2") (pintype "bidirectional"))
    )
    (net (code "89") (name "/PE4") (class "Default")
      (node (ref "J4") (pin "10") (pinfunction "10_10") (pintype "passive"))
      (node (ref "U2") (pin "3") (pinfunction "PE4_3") (pintype "bidirectional"))
    )
    (net (code "90") (name "/PE5") (class "Default")
      (node (ref "J4") (pin "8") (pinfunction "8_8") (pintype "passive"))
      (node (ref "U2") (pin "4") (pinfunction "PE5_4") (pintype "bidirectional"))
    )
    (net (code "91") (name "/PE6") (class "Default")
      (node (ref "J4") (pin "6") (pinfunction "6_6") (pintype "passive"))
      (node (ref "U2") (pin "5") (pinfunction "PE6_5") (pintype "bidirectional"))
    )
    (net (code "92") (name "/PE7") (class "Default")
      (node (ref "J3") (pin "42") (pinfunction "42_42") (pintype "passive"))
      (node (ref "U2") (pin "38") (pinfunction "PE7_38") (pintype "bidirectional"))
    )
    (net (code "93") (name "/PE8") (class "Default")
      (node (ref "J3") (pin "43") (pinfunction "43_43") (pintype "passive"))
      (node (ref "U2") (pin "39") (pinfunction "PE8_39") (pintype "bidirectional"))
    )
    (net (code "94") (name "/PE9") (class "Default")
      (node (ref "J3") (pin "44") (pinfunction "44_44") (pintype "passive"))
      (node (ref "U2") (pin "40") (pinfunction "PE9_40") (pintype "bidirectional"))
    )
    (net (code "95") (name "/PE10") (class "Default")
      (node (ref "J3") (pin "45") (pinfunction "45_45") (pintype "passive"))
      (node (ref "U2") (pin "41") (pinfunction "PE10_41") (pintype "bidirectional"))
    )
    (net (code "96") (name "/PE11") (class "Default")
      (node (ref "J3") (pin "46") (pinfunction "46_46") (pintype "passive"))
      (node (ref "U2") (pin "42") (pinfunction "PE11_42") (pintype "bidirectional"))
    )
    (net (code "97") (name "/PE12") (class "Default")
      (node (ref "J3") (pin "47") (pinfunction "47_47") (pintype "passive"))
      (node (ref "U2") (pin "43") (pinfunction "PE12_43") (pintype "bidirectional"))
    )
    (net (code "98") (name "/PE13") (class "Default")
      (node (ref "J3") (pin "48") (pinfunction "48_48") (pintype "passive"))
      (node (ref "U2") (pin "44") (pinfunction "PE13_44") (pintype "bidirectional"))
    )
    (net (code "99") (name "/PE14") (class "Default")
      (node (ref "J3") (pin "49") (pinfunction "49_49") (pintype "passive"))
      (node (ref "U2") (pin "45") (pinfunction "PE14_45") (pintype "bidirectional"))
    )
    (net (code "100") (name "/PE15") (class "Default")
      (node (ref "J3") (pin "50") (pinfunction "50_50") (pintype "passive"))
      (node (ref "U2") (pin "46") (pinfunction "PE15_46") (pintype "bidirectional"))
    )
    (net (code "101") (name "/RST0") (class "Default")
      (node (ref "J2") (pin "8") (pinfunction "8_8") (pintype "passive"))
      (node (ref "U3") (pin "11") (pinfunction "PC8_11") (pintype "bidirectional"))
    )
    (net (code "102") (name "/RT") (class "Default")
      (node (ref "RT") (pin "1") (pinfunction "point_1") (pintype "passive"))
      (node (ref "U3") (pin "1") (pinfunction "RST#_1") (pintype "input"))
    )
    (net (code "103") (name "/RX_OUT") (class "Default")
      (node (ref "J2") (pin "9") (pinfunction "9_9") (pintype "passive"))
      (node (ref "R33") (pin "1") (pinfunction "1_1") (pintype "passive"))
    )
    (net (code "104") (name "/TX_OUT") (class "Default")
      (node (ref "J2") (pin "11") (pinfunction "11_11") (pintype "passive"))
      (node (ref "R34") (pin "1") (pinfunction "1_1") (pintype "passive"))
    )
    (net (code "105") (name "/UART3_RX") (class "Default")
      (node (ref "R33") (pin "2") (pinfunction "2_2") (pintype "passive"))
      (node (ref "U3") (pin "4") (pinfunction "PB11/UART3_RX/I2C2_SDA_4") (pintype "bidirectional"))
    )
    (net (code "106") (name "/UART3_TX") (class "Default")
      (node (ref "R34") (pin "2") (pinfunction "2_2") (pintype "passive"))
      (node (ref "U3") (pin "3") (pinfunction "PB10/UART3_TX/I2C2_SCL_3") (pintype "bidirectional"))
    )
    (net (code "107") (name "/USB_N") (class "Default")
      (node (ref "P9") (pin "A7") (pinfunction "D-_A7") (pintype "bidirectional"))
      (node (ref "P9") (pin "B7") (pinfunction "D-_B7") (pintype "bidirectional"))
      (node (ref "U3") (pin "16") (pinfunction "PB6/USB2DM/UART1X_TX_16") (pintype "bidirectional"))
    )
    (net (code "108") (name "/USB_P") (class "Default")
      (node (ref "P9") (pin "A6") (pinfunction "D+_A6") (pintype "bidirectional"))
      (node (ref "P9") (pin "B6") (pinfunction "D+_B6") (pintype "bidirectional"))
      (node (ref "U3") (pin "17") (pinfunction "PB7/USB2DP/UART1X_RX_17") (pintype "bidirectional"))
    )
    (net (code "109") (name "/VBAT") (class "Default")
      (node (ref "C9") (pin "2") (pinfunction "2_2") (pintype "passive"))
      (node (ref "J4") (pin "4") (pinfunction "4_4") (pintype "passive"))
      (node (ref "U2") (pin "6") (pinfunction "VBAT_6") (pintype "power_in"))
    )
    (net (code "110") (name "/VDDA") (class "Default")
      (node (ref "C10") (pin "2") (pinfunction "2_2") (pintype "passive"))
      (node (ref "J4") (pin "5") (pinfunction "5_5") (pintype "passive"))
      (node (ref "J7") (pin "3") (pinfunction "3_3") (pintype "passive"))
      (node (ref "R15") (pin "2") (pinfunction "2_2") (pintype "passive"))
      (node (ref "R16") (pin "1") (pinfunction "1_1") (pintype "passive"))
      (node (ref "U2") (pin "22") (pinfunction "VDDA_22") (pintype "power_in"))
    )
    (net (code "111") (name "/VIO") (class "Default")
      (node (ref "C1") (pin "2") (pinfunction "2_2") (pintype "passive"))
      (node (ref "C3") (pin "1") (pinfunction "1_1") (pintype "passive"))
      (node (ref "J4") (pin "44") (pinfunction "44_44") (pintype "passive"))
      (node (ref "R15") (pin "1") (pinfunction "1_1") (pintype "passive"))
      (node (ref "R22") (pin "1") (pinfunction "1_1") (pintype "passive"))
      (node (ref "U2") (pin "100") (pinfunction "VIO_3_100") (pintype "power_in"))
      (node (ref "U2") (pin "50") (pinfunction "VIO_1_50") (pintype "power_in"))
    )
    (net (code "112") (name "/VREF+") (class "Default")
      (node (ref "R16") (pin "2") (pinfunction "2_2") (pintype "passive"))
      (node (ref "U2") (pin "21") (pinfunction "VREF+_21") (pintype "power_in"))
    )
    (net (code "113") (name "/VREF-") (class "Default")
      (node (ref "R18") (pin "2") (pinfunction "2_2") (pintype "passive"))
      (node (ref "U2") (pin "20") (pinfunction "VREF-_20") (pintype "power_in"))
    )
    (net (code "114") (name "/XI") (class "Default")
      (node (ref "C7") (pin "2") (pinfunction "2_2") (pintype "passive"))
      (node (ref "U2") (pin "12") (pinfunction "OSC_IN_12") (pintype "input"))
      (node (ref "Y1") (pin "1") (pinfunction "OSC1_1") (pintype "passive"))
    )
    (net (code "115") (name "/XO") (class "Default")
      (node (ref "C8") (pin "2") (pinfunction "2_2") (pintype "passive"))
      (node (ref "U2") (pin "13") (pinfunction "OSC_OUT_13") (pintype "output"))
      (node (ref "Y1") (pin "3") (pinfunction "OSC2_3") (pintype "passive"))
    )
    (net (code "116") (name "3V3") (class "Default")
      (node (ref "C2") (pin "2") (pinfunction "2_2") (pintype "passive"))
      (node (ref "C21") (pin "1") (pinfunction "1_1") (pintype "passive"))
      (node (ref "C4") (pin "2") (pinfunction "2_2") (pintype "passive"))
      (node (ref "C46") (pin "1") (pinfunction "1_1") (pintype "passive"))
      (node (ref "D2") (pin "1") (pinfunction "A_1") (pintype "passive"))
      (node (ref "D3") (pin "1") (pinfunction "A_1") (pintype "passive"))
      (node (ref "J2") (pin "7") (pinfunction "7_7") (pintype "passive"))
      (node (ref "J3") (pin "1") (pinfunction "1_1") (pintype "passive"))
      (node (ref "J3") (pin "12") (pinfunction "12_12") (pintype "passive"))
      (node (ref "J3") (pin "15") (pinfunction "15_15") (pintype "passive"))
      (node (ref "J3") (pin "16") (pinfunction "16_16") (pintype "passive"))
      (node (ref "J3") (pin "2") (pinfunction "2_2") (pintype "passive"))
      (node (ref "J3") (pin "3") (pinfunction "3_3") (pintype "passive"))
      (node (ref "J3") (pin "4") (pinfunction "4_4") (pintype "passive"))
      (node (ref "J5") (pin "2") (pinfunction "2_2") (pintype "passive"))
      (node (ref "J5") (pin "4") (pinfunction "4_4") (pintype "passive"))
      (node (ref "R1") (pin "2") (pinfunction "2_2") (pintype "passive"))
      (node (ref "R14") (pin "2") (pinfunction "2_2") (pintype "passive"))
      (node (ref "R2") (pin "1") (pinfunction "1_1") (pintype "passive"))
      (node (ref "R22") (pin "2") (pinfunction "2_2") (pintype "passive"))
      (node (ref "R24") (pin "2") (pinfunction "2_2") (pintype "passive"))
      (node (ref "R3") (pin "1") (pinfunction "1_1") (pintype "passive"))
      (node (ref "S3") (pin "3") (pinfunction "3_3") (pintype "passive"))
      (node (ref "U2") (pin "11") (pinfunction "VDD_5_11") (pintype "power_in"))
      (node (ref "U2") (pin "28") (pinfunction "VDD_4_28") (pintype "power_in"))
      (node (ref "U2") (pin "75") (pinfunction "VDD_2_75") (pintype "power_in"))
      (node (ref "U3") (pin "14") (pinfunction "VDD33/VIO_14") (pintype "power_in"))
    )
    (net (code "117") (name "5V_in") (class "Default")
      (node (ref "F2") (pin "1") (pinfunction "1_1") (pintype "passive"))
      (node (ref "P7") (pin "A4") (pinfunction "VBUS_A4") (pintype "bidirectional"))
      (node (ref "P7") (pin "B4") (pinfunction "VBUS_B4") (pintype "bidirectional"))
      (node (ref "P9") (pin "A4") (pinfunction "VBUS_A4") (pintype "bidirectional"))
      (node (ref "P9") (pin "B4") (pinfunction "VBUS_B4") (pintype "bidirectional"))
    )
    (net (code "118") (name "GND") (class "Default")
      (node (ref "C1") (pin "1") (pinfunction "1_1") (pintype "passive"))
      (node (ref "C10") (pin "1") (pinfunction "1_1") (pintype "passive"))
      (node (ref "C11") (pin "1") (pinfunction "1_1") (pintype "passive"))
      (node (ref "C12") (pin "2") (pinfunction "2_2") (pintype "passive"))
      (node (ref "C13") (pin "2") (pinfunction "2_2") (pintype "passive"))
      (node (ref "C2") (pin "1") (pinfunction "1_1") (pintype "passive"))
      (node (ref "C21") (pin "2") (pinfunction "2_2") (pintype "passive"))
      (node (ref "C3") (pin "2") (pinfunction "2_2") (pintype "passive"))
      (node (ref "C31") (pin "1") (pinfunction "1_1") (pintype "passive"))
      (node (ref "C32") (pin "1") (pinfunction "1_1") (pintype "passive"))
      (node (ref "C4") (pin "1") (pinfunction "1_1") (pintype "passive"))
      (node (ref "C46") (pin "2") (pinfunction "2_2") (pintype "passive"))
      (node (ref "C5") (pin "2") (pinfunction "2_2") (pintype "passive"))
      (node (ref "C6") (pin "2") (pinfunction "2_2") (pintype "passive"))
      (node (ref "C7") (pin "1") (pinfunction "1_1") (pintype "passive"))
      (node (ref "C8") (pin "1") (pinfunction "1_1") (pintype "passive"))
      (node (ref "C9") (pin "1") (pinfunction "1_1") (pintype "passive"))
      (node (ref "J2") (pin "5") (pinfunction "5_5") (pintype "passive"))
      (node (ref "J2") (pin "6") (pinfunction "6_6") (pintype "passive"))
      (node (ref "J3") (pin "20") (pinfunction "20_20") (pintype "passive"))
      (node (ref "J3") (pin "22") (pinfunction "22_22") (pintype "passive"))
      (node (ref "J3") (pin "25") (pinfunction "25_25") (pintype "passive"))
      (node (ref "J3") (pin "26") (pinfunction "26_26") (pintype "passive"))
      (node (ref "J3") (pin "7") (pinfunction "7_7") (pintype "passive"))
      (node (ref "J3") (pin "8") (pinfunction "8_8") (pintype "passive"))
      (node (ref "J3") (pin "9") (pinfunction "9_9") (pintype "passive"))
      (node (ref "J4") (pin "7") (pinfunction "7_7") (pintype "passive"))
      (node (ref "J5") (pin "6") (pinfunction "6_6") (pintype "passive"))
      (node (ref "J5") (pin "7") (pinfunction "7_7") (pintype "passive"))
      (node (ref "J7") (pin "4") (pinfunction "4_4") (pintype "passive"))
      (node (ref "P7") (pin "A1") (pinfunction "GND_A1") (pintype "bidirectional"))
      (node (ref "P7") (pin "B1") (pinfunction "GND_B1") (pintype "bidirectional"))
      (node (ref "P9") (pin "A1") (pinfunction "GND_A1") (pintype "bidirectional"))
      (node (ref "P9") (pin "B1") (pinfunction "GND_B1") (pintype "bidirectional"))
      (node (ref "PWR") (pin "2") (pinfunction "K_2") (pintype "passive"))
      (node (ref "R10") (pin "2") (pinfunction "2_2") (pintype "passive"))
      (node (ref "R11") (pin "2") (pinfunction "2_2") (pintype "passive"))
      (node (ref "R18") (pin "1") (pinfunction "1_1") (pintype "passive"))
      (node (ref "R21") (pin "1") (pinfunction "1_1") (pintype "passive"))
      (node (ref "R8") (pin "1") (pinfunction "1_1") (pintype "passive"))
      (node (ref "R9") (pin "1") (pinfunction "1_1") (pintype "passive"))
      (node (ref "S1") (pin "3") (pinfunction "B1_3") (pintype "passive"))
      (node (ref "S2") (pin "3") (pinfunction "B1_3") (pintype "passive"))
      (node (ref "S5") (pin "2") (pinfunction "2_2") (pintype "passive"))
      (node (ref "U1") (pin "1") (pinfunction "GND_1") (pintype "passive"))
      (node (ref "U2") (pin "10") (pinfunction "VSS_5_10") (pintype "power_in"))
      (node (ref "U2") (pin "19") (pinfunction "VSSA_19") (pintype "power_in"))
      (node (ref "U2") (pin "27") (pinfunction "VSS_4_27") (pintype "power_in"))
      (node (ref "U2") (pin "49") (pinfunction "VSS_1_49") (pintype "power_in"))
      (node (ref "U2") (pin "74") (pinfunction "VSS_2_74") (pintype "power_in"))
      (node (ref "U2") (pin "99") (pinfunction "VSS_3_99") (pintype "power_in"))
      (node (ref "U3") (pin "18") (pinfunction "VSS/GND_18") (pintype "power_in"))
    )
    (net (code "119") (name "Net-(D2-K)") (class "Default")
      (node (ref "D2") (pin "2") (pinfunction "K_2") (pintype "passive"))
      (node (ref "R13") (pin "2") (pinfunction "2_2") (pintype "passive"))
    )
    (net (code "120") (name "Net-(D3-K)") (class "Default")
      (node (ref "D3") (pin "2") (pinfunction "K_2") (pintype "passive"))
      (node (ref "R21") (pin "2") (pinfunction "2_2") (pintype "passive"))
    )
    (net (code "121") (name "Net-(J3-Pad6)") (class "Default")
      (node (ref "J3") (pin "6") (pinfunction "6_6") (pintype "passive"))
      (node (ref "R5") (pin "1") (pinfunction "1_1") (pintype "passive"))
    )
    (net (code "122") (name "Net-(J3-Pad10)") (class "Default")
      (node (ref "J3") (pin "10") (pinfunction "10_10") (pintype "passive"))
      (node (ref "J5") (pin "1") (pinfunction "1_1") (pintype "passive"))
    )
    (net (code "123") (name "Net-(LED1-A)") (class "Default")
      (node (ref "LED1") (pin "1") (pinfunction "A_1") (pintype "passive"))
      (node (ref "R2") (pin "2") (pinfunction "2_2") (pintype "passive"))
    )
    (net (code "124") (name "Net-(LED2-A)") (class "Default")
      (node (ref "LED2") (pin "1") (pinfunction "A_1") (pintype "passive"))
      (node (ref "R3") (pin "2") (pinfunction "2_2") (pintype "passive"))
    )
    (net (code "125") (name "Net-(P7-CC-PadA5)") (class "Default")
      (node (ref "P7") (pin "A5") (pinfunction "CC_A5") (pintype "bidirectional"))
      (node (ref "R8") (pin "2") (pinfunction "2_2") (pintype "passive"))
    )
    (net (code "126") (name "Net-(P7-CC-PadB5)") (class "Default")
      (node (ref "P7") (pin "B5") (pinfunction "CC_B5") (pintype "bidirectional"))
      (node (ref "R9") (pin "2") (pinfunction "2_2") (pintype "passive"))
    )
    (net (code "127") (name "Net-(P9-CC-PadA5)") (class "Default")
      (node (ref "P9") (pin "A5") (pinfunction "CC_A5") (pintype "bidirectional"))
      (node (ref "R10") (pin "1") (pinfunction "1_1") (pintype "passive"))
    )
    (net (code "128") (name "Net-(P9-CC-PadB5)") (class "Default")
      (node (ref "P9") (pin "B5") (pinfunction "CC_B5") (pintype "bidirectional"))
      (node (ref "R11") (pin "1") (pinfunction "1_1") (pintype "passive"))
    )
    (net (code "129") (name "Net-(PWR-A)") (class "Default")
      (node (ref "PWR") (pin "1") (pinfunction "A_1") (pintype "passive"))
      (node (ref "R1") (pin "1") (pinfunction "1_1") (pintype "passive"))
    )
    (net (code "130") (name "Net-(U1-VOUT)") (class "Default")
      (node (ref "C13") (pin "1") (pinfunction "1_1") (pintype "passive"))
      (node (ref "S3") (pin "1") (pinfunction "1_1") (pintype "passive"))
      (node (ref "U1") (pin "2") (pinfunction "VOUT_2") (pintype "passive"))
    )
    (net (code "131") (name "unconnected-(P7-RFU1-PadA8)") (class "Default")
      (node (ref "P7") (pin "A8") (pinfunction "RFU1_A8") (pintype "bidirectional+no_connect"))
    )
    (net (code "132") (name "unconnected-(P7-RFU1-PadB8)") (class "Default")
      (node (ref "P7") (pin "B8") (pinfunction "RFU1_B8") (pintype "bidirectional+no_connect"))
    )
    (net (code "133") (name "unconnected-(P9-RFU1-PadA8)") (class "Default")
      (node (ref "P9") (pin "A8") (pinfunction "RFU1_A8") (pintype "bidirectional+no_connect"))
    )
    (net (code "134") (name "unconnected-(P9-RFU1-PadB8)") (class "Default")
      (node (ref "P9") (pin "B8") (pinfunction "RFU1_B8") (pintype "bidirectional+no_connect"))
    )
    (net (code "135") (name "unconnected-(S1-A1-Pad4)") (class "Default")
      (node (ref "S1") (pin "4") (pinfunction "A1_4") (pintype "passive"))
    )
    (net (code "136") (name "unconnected-(S1-B0-Pad2)") (class "Default")
      (node (ref "S1") (pin "2") (pinfunction "B0_2") (pintype "passive"))
    )
    (net (code "137") (name "unconnected-(S2-A1-Pad4)") (class "Default")
      (node (ref "S2") (pin "4") (pinfunction "A1_4") (pintype "passive"))
    )
    (net (code "138") (name "unconnected-(S2-B0-Pad2)") (class "Default")
      (node (ref "S2") (pin "2") (pinfunction "B0_2") (pintype "passive"))
    )
    (net (code "139") (name "unconnected-(S3-Pad2)") (class "Default")
      (node (ref "S3") (pin "2") (pinfunction "2_2") (pintype "passive"))
    )
    (net (code "140") (name "unconnected-(U3-PA5{slash}UART1_CTS{slash}PA1_(no5V)-Pad2)") (class "Default")
      (node (ref "U3") (pin "2") (pinfunction "PA5/UART1_CTS/PA1_(no5V)_2") (pintype "bidirectional+no_connect"))
    )
    (net (code "141") (name "unconnected-(U3-PB12{slash}SPI2_NSS{slash}CAN2_RX-Pad5)") (class "Default")
      (node (ref "U3") (pin "5") (pinfunction "PB12/SPI2_NSS/CAN2_RX_5") (pintype "bidirectional+no_connect"))
    )
    (net (code "142") (name "unconnected-(U3-PB14{slash}SPI2_MISO{slash}UART3_RTS-Pad7)") (class "Default")
      (node (ref "U3") (pin "7") (pinfunction "PB14/SPI2_MISO/UART3_RTS_7") (pintype "bidirectional+no_connect"))
    )
    (net (code "143") (name "unconnected-(U3-PB15{slash}SPI2_MOSI{slash}UART1_TX-Pad8)") (class "Default")
      (node (ref "U3") (pin "8") (pinfunction "PB15/SPI2_MOSI/UART1_TX_8") (pintype "bidirectional+no_connect"))
    )
  )
)
